# NumPad.net
KiCad netlist of a schematic drawn in EAGLE
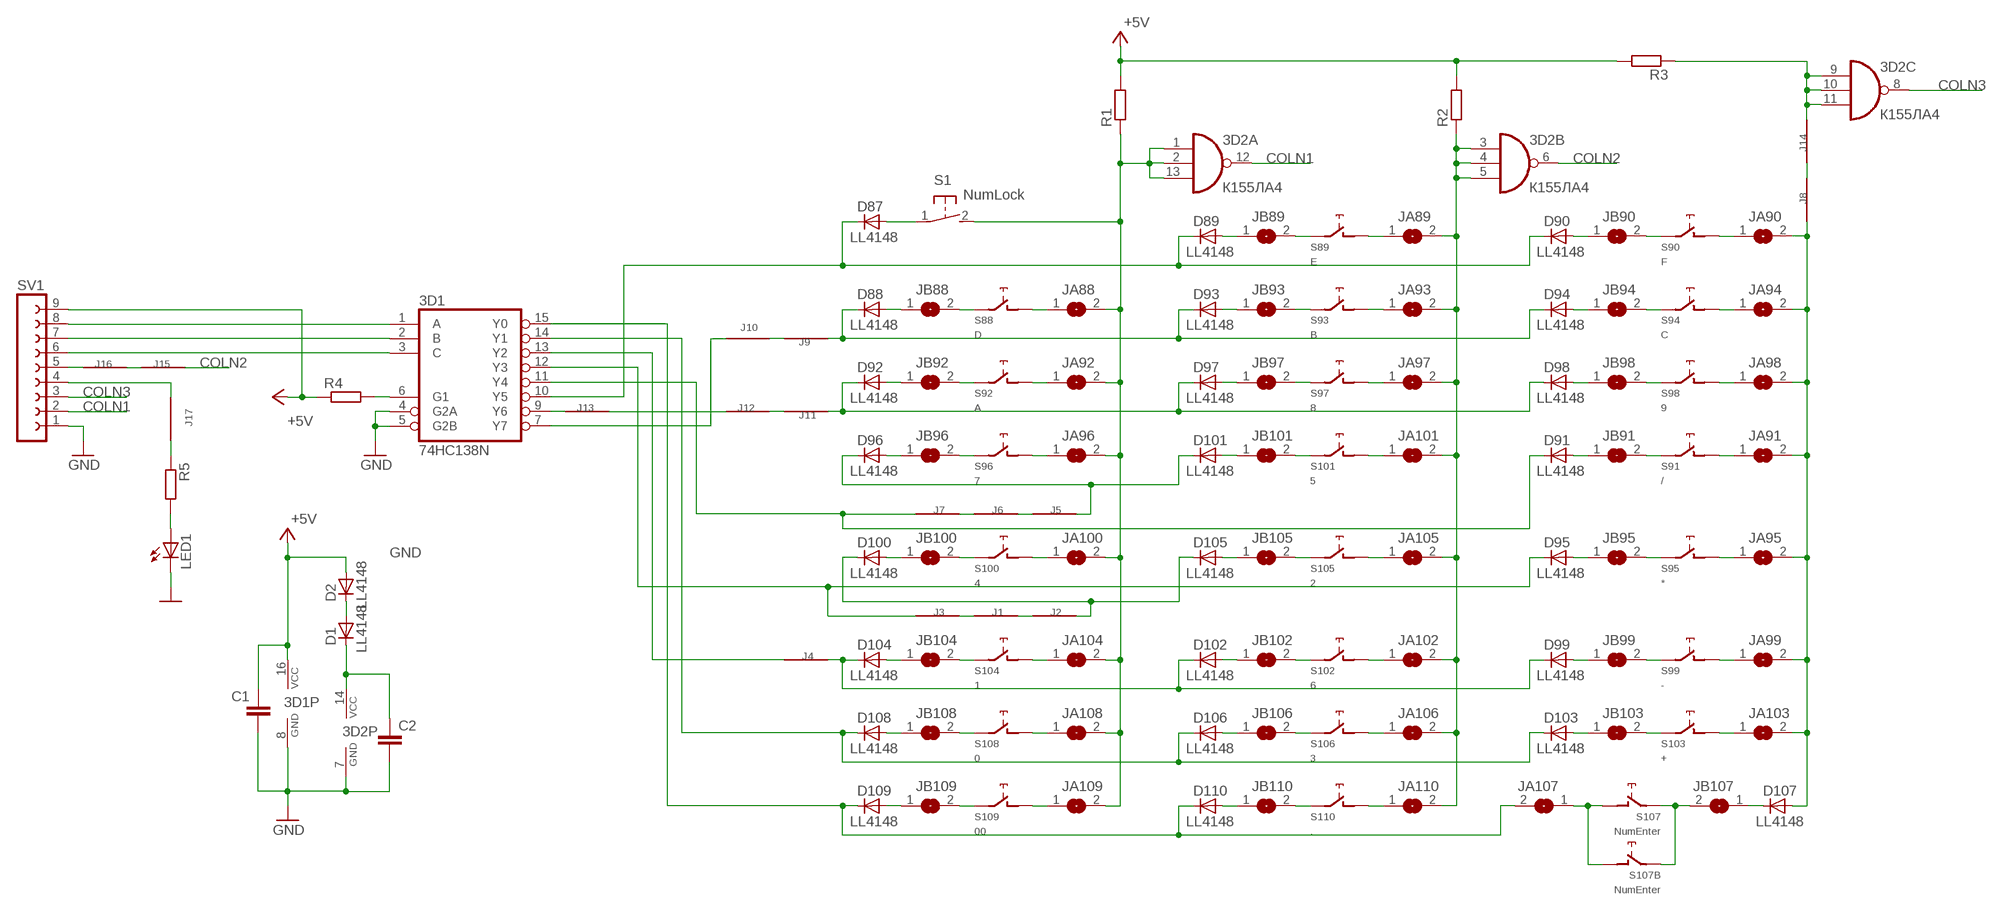
[diagram p0: schematic, sheet 1]

(export (version "E")
  (design (tool "Eeschema 10.0.6"))
  (components
    (comp (ref "3D1")
      (value "74HC138N")
      (footprint "eagle-import:DIL16")
      (libsource (lib "eagle-import") (part "74138NHC"))
    )
    (comp (ref "3D2")
      (value "К155ЛА4")
      (footprint "eagle-import:DIL14")
      (libsource (lib "eagle-import") (part "7410NHC"))
    )
    (comp (ref "C1")
      (value "C-EUC1206")
      (footprint "eagle-import:C1206")
      (libsource (lib "eagle-import") (part "C-EUC1206"))
    )
    (comp (ref "C2")
      (value "C-EUC1206")
      (footprint "eagle-import:C1206")
      (libsource (lib "eagle-import") (part "C-EUC1206"))
    )
    (comp (ref "D1")
      (value "LL4148")
      (footprint "eagle-import:SOD80C")
      (libsource (lib "eagle-import") (part "LL4148"))
    )
    (comp (ref "D2")
      (value "LL4148")
      (footprint "eagle-import:SOD80C")
      (libsource (lib "eagle-import") (part "LL4148"))
    )
    (comp (ref "D87")
      (value "LL4148")
      (footprint "eagle-import:SOD80C")
      (libsource (lib "eagle-import") (part "LL4148"))
    )
    (comp (ref "D88")
      (value "LL4148")
      (footprint "eagle-import:SOD80C")
      (libsource (lib "eagle-import") (part "LL4148"))
    )
    (comp (ref "D89")
      (value "LL4148")
      (footprint "eagle-import:SOD80C")
      (libsource (lib "eagle-import") (part "LL4148"))
    )
    (comp (ref "D90")
      (value "LL4148")
      (footprint "eagle-import:SOD80C")
      (libsource (lib "eagle-import") (part "LL4148"))
    )
    (comp (ref "D91")
      (value "LL4148")
      (footprint "eagle-import:SOD80C")
      (libsource (lib "eagle-import") (part "LL4148"))
    )
    (comp (ref "D92")
      (value "LL4148")
      (footprint "eagle-import:SOD80C")
      (libsource (lib "eagle-import") (part "LL4148"))
    )
    (comp (ref "D93")
      (value "LL4148")
      (footprint "eagle-import:SOD80C")
      (libsource (lib "eagle-import") (part "LL4148"))
    )
    (comp (ref "D94")
      (value "LL4148")
      (footprint "eagle-import:SOD80C")
      (libsource (lib "eagle-import") (part "LL4148"))
    )
    (comp (ref "D95")
      (value "LL4148")
      (footprint "eagle-import:SOD80C")
      (libsource (lib "eagle-import") (part "LL4148"))
    )
    (comp (ref "D96")
      (value "LL4148")
      (footprint "eagle-import:SOD80C")
      (libsource (lib "eagle-import") (part "LL4148"))
    )
    (comp (ref "D97")
      (value "LL4148")
      (footprint "eagle-import:SOD80C")
      (libsource (lib "eagle-import") (part "LL4148"))
    )
    (comp (ref "D98")
      (value "LL4148")
      (footprint "eagle-import:SOD80C")
      (libsource (lib "eagle-import") (part "LL4148"))
    )
    (comp (ref "D99")
      (value "LL4148")
      (footprint "eagle-import:SOD80C")
      (libsource (lib "eagle-import") (part "LL4148"))
    )
    (comp (ref "D100")
      (value "LL4148")
      (footprint "eagle-import:SOD80C")
      (libsource (lib "eagle-import") (part "LL4148"))
    )
    (comp (ref "D101")
      (value "LL4148")
      (footprint "eagle-import:SOD80C")
      (libsource (lib "eagle-import") (part "LL4148"))
    )
    (comp (ref "D102")
      (value "LL4148")
      (footprint "eagle-import:SOD80C")
      (libsource (lib "eagle-import") (part "LL4148"))
    )
    (comp (ref "D103")
      (value "LL4148")
      (footprint "eagle-import:SOD80C")
      (libsource (lib "eagle-import") (part "LL4148"))
    )
    (comp (ref "D104")
      (value "LL4148")
      (footprint "eagle-import:SOD80C")
      (libsource (lib "eagle-import") (part "LL4148"))
    )
    (comp (ref "D105")
      (value "LL4148")
      (footprint "eagle-import:SOD80C")
      (libsource (lib "eagle-import") (part "LL4148"))
    )
    (comp (ref "D106")
      (value "LL4148")
      (footprint "eagle-import:SOD80C")
      (libsource (lib "eagle-import") (part "LL4148"))
    )
    (comp (ref "D107")
      (value "LL4148")
      (footprint "eagle-import:SOD80C")
      (libsource (lib "eagle-import") (part "LL4148"))
    )
    (comp (ref "D108")
      (value "LL4148")
      (footprint "eagle-import:SOD80C")
      (libsource (lib "eagle-import") (part "LL4148"))
    )
    (comp (ref "D109")
      (value "LL4148")
      (footprint "eagle-import:SOD80C")
      (libsource (lib "eagle-import") (part "LL4148"))
    )
    (comp (ref "D110")
      (value "LL4148")
      (footprint "eagle-import:SOD80C")
      (libsource (lib "eagle-import") (part "LL4148"))
    )
    (comp (ref "J1")
      (value "J")
      (footprint "eagle-import:R1206W")
      (libsource (lib "eagle-import") (part "J"))
    )
    (comp (ref "J2")
      (value "J")
      (footprint "eagle-import:R1206W")
      (libsource (lib "eagle-import") (part "J"))
    )
    (comp (ref "J3")
      (value "J")
      (footprint "eagle-import:R1206W")
      (libsource (lib "eagle-import") (part "J"))
    )
    (comp (ref "J4")
      (value "J")
      (footprint "eagle-import:R1206W")
      (libsource (lib "eagle-import") (part "J"))
    )
    (comp (ref "J5")
      (value "J")
      (footprint "eagle-import:R1206W")
      (libsource (lib "eagle-import") (part "J"))
    )
    (comp (ref "J6")
      (value "J")
      (footprint "eagle-import:R1206W")
      (libsource (lib "eagle-import") (part "J"))
    )
    (comp (ref "J7")
      (value "J")
      (footprint "eagle-import:R1206W")
      (libsource (lib "eagle-import") (part "J"))
    )
    (comp (ref "J8")
      (value "J")
      (footprint "eagle-import:R1206W")
      (libsource (lib "eagle-import") (part "J"))
    )
    (comp (ref "J9")
      (value "J")
      (footprint "eagle-import:R1206W")
      (libsource (lib "eagle-import") (part "J"))
    )
    (comp (ref "J10")
      (value "J")
      (footprint "eagle-import:R1206W")
      (libsource (lib "eagle-import") (part "J"))
    )
    (comp (ref "J11")
      (value "J")
      (footprint "eagle-import:R1206W")
      (libsource (lib "eagle-import") (part "J"))
    )
    (comp (ref "J12")
      (value "J")
      (footprint "eagle-import:R1206W")
      (libsource (lib "eagle-import") (part "J"))
    )
    (comp (ref "J13")
      (value "J")
      (footprint "eagle-import:R1206W")
      (libsource (lib "eagle-import") (part "J"))
    )
    (comp (ref "J14")
      (value "J")
      (footprint "eagle-import:R1206W")
      (libsource (lib "eagle-import") (part "J"))
    )
    (comp (ref "J15")
      (value "J")
      (footprint "eagle-import:R1206W")
      (libsource (lib "eagle-import") (part "J"))
    )
    (comp (ref "J16")
      (value "J")
      (footprint "eagle-import:R1206W")
      (libsource (lib "eagle-import") (part "J"))
    )
    (comp (ref "J17")
      (value "J")
      (footprint "eagle-import:R1206W")
      (libsource (lib "eagle-import") (part "J"))
    )
    (comp (ref "JA88")
      (value "SJ")
      (footprint "eagle-import:SJ")
      (libsource (lib "eagle-import") (part "SJ"))
    )
    (comp (ref "JA89")
      (value "SJ")
      (footprint "eagle-import:SJ")
      (libsource (lib "eagle-import") (part "SJ"))
    )
    (comp (ref "JA90")
      (value "SJ")
      (footprint "eagle-import:SJ")
      (libsource (lib "eagle-import") (part "SJ"))
    )
    (comp (ref "JA91")
      (value "SJ")
      (footprint "eagle-import:SJ")
      (libsource (lib "eagle-import") (part "SJ"))
    )
    (comp (ref "JA92")
      (value "SJ")
      (footprint "eagle-import:SJ")
      (libsource (lib "eagle-import") (part "SJ"))
    )
    (comp (ref "JA93")
      (value "SJ")
      (footprint "eagle-import:SJ")
      (libsource (lib "eagle-import") (part "SJ"))
    )
    (comp (ref "JA94")
      (value "SJ")
      (footprint "eagle-import:SJ")
      (libsource (lib "eagle-import") (part "SJ"))
    )
    (comp (ref "JA95")
      (value "SJ")
      (footprint "eagle-import:SJ")
      (libsource (lib "eagle-import") (part "SJ"))
    )
    (comp (ref "JA96")
      (value "SJ")
      (footprint "eagle-import:SJ")
      (libsource (lib "eagle-import") (part "SJ"))
    )
    (comp (ref "JA97")
      (value "SJ")
      (footprint "eagle-import:SJ")
      (libsource (lib "eagle-import") (part "SJ"))
    )
    (comp (ref "JA98")
      (value "SJ")
      (footprint "eagle-import:SJ")
      (libsource (lib "eagle-import") (part "SJ"))
    )
    (comp (ref "JA99")
      (value "SJ")
      (footprint "eagle-import:SJ")
      (libsource (lib "eagle-import") (part "SJ"))
    )
    (comp (ref "JA100")
      (value "SJ")
      (footprint "eagle-import:SJ")
      (libsource (lib "eagle-import") (part "SJ"))
    )
    (comp (ref "JA101")
      (value "SJ")
      (footprint "eagle-import:SJ")
      (libsource (lib "eagle-import") (part "SJ"))
    )
    (comp (ref "JA102")
      (value "SJ")
      (footprint "eagle-import:SJ")
      (libsource (lib "eagle-import") (part "SJ"))
    )
    (comp (ref "JA103")
      (value "SJ")
      (footprint "eagle-import:SJ")
      (libsource (lib "eagle-import") (part "SJ"))
    )
    (comp (ref "JA104")
      (value "SJ")
      (footprint "eagle-import:SJ")
      (libsource (lib "eagle-import") (part "SJ"))
    )
    (comp (ref "JA105")
      (value "SJ")
      (footprint "eagle-import:SJ")
      (libsource (lib "eagle-import") (part "SJ"))
    )
    (comp (ref "JA106")
      (value "SJ")
      (footprint "eagle-import:SJ")
      (libsource (lib "eagle-import") (part "SJ"))
    )
    (comp (ref "JA107")
      (value "SJ")
      (footprint "eagle-import:SJ")
      (libsource (lib "eagle-import") (part "SJ"))
    )
    (comp (ref "JA108")
      (value "SJ")
      (footprint "eagle-import:SJ")
      (libsource (lib "eagle-import") (part "SJ"))
    )
    (comp (ref "JA109")
      (value "SJ")
      (footprint "eagle-import:SJ")
      (libsource (lib "eagle-import") (part "SJ"))
    )
    (comp (ref "JA110")
      (value "SJ")
      (footprint "eagle-import:SJ")
      (libsource (lib "eagle-import") (part "SJ"))
    )
    (comp (ref "JB88")
      (value "SJ")
      (footprint "eagle-import:SJ")
      (libsource (lib "eagle-import") (part "SJ"))
    )
    (comp (ref "JB89")
      (value "SJ")
      (footprint "eagle-import:SJ")
      (libsource (lib "eagle-import") (part "SJ"))
    )
    (comp (ref "JB90")
      (value "SJ")
      (footprint "eagle-import:SJ")
      (libsource (lib "eagle-import") (part "SJ"))
    )
    (comp (ref "JB91")
      (value "SJ")
      (footprint "eagle-import:SJ")
      (libsource (lib "eagle-import") (part "SJ"))
    )
    (comp (ref "JB92")
      (value "SJ")
      (footprint "eagle-import:SJ")
      (libsource (lib "eagle-import") (part "SJ"))
    )
    (comp (ref "JB93")
      (value "SJ")
      (footprint "eagle-import:SJ")
      (libsource (lib "eagle-import") (part "SJ"))
    )
    (comp (ref "JB94")
      (value "SJ")
      (footprint "eagle-import:SJ")
      (libsource (lib "eagle-import") (part "SJ"))
    )
    (comp (ref "JB95")
      (value "SJ")
      (footprint "eagle-import:SJ")
      (libsource (lib "eagle-import") (part "SJ"))
    )
    (comp (ref "JB96")
      (value "SJ")
      (footprint "eagle-import:SJ")
      (libsource (lib "eagle-import") (part "SJ"))
    )
    (comp (ref "JB97")
      (value "SJ")
      (footprint "eagle-import:SJ")
      (libsource (lib "eagle-import") (part "SJ"))
    )
    (comp (ref "JB98")
      (value "SJ")
      (footprint "eagle-import:SJ")
      (libsource (lib "eagle-import") (part "SJ"))
    )
    (comp (ref "JB99")
      (value "SJ")
      (footprint "eagle-import:SJ")
      (libsource (lib "eagle-import") (part "SJ"))
    )
    (comp (ref "JB100")
      (value "SJ")
      (footprint "eagle-import:SJ")
      (libsource (lib "eagle-import") (part "SJ"))
    )
    (comp (ref "JB101")
      (value "SJ")
      (footprint "eagle-import:SJ")
      (libsource (lib "eagle-import") (part "SJ"))
    )
    (comp (ref "JB102")
      (value "SJ")
      (footprint "eagle-import:SJ")
      (libsource (lib "eagle-import") (part "SJ"))
    )
    (comp (ref "JB103")
      (value "SJ")
      (footprint "eagle-import:SJ")
      (libsource (lib "eagle-import") (part "SJ"))
    )
    (comp (ref "JB104")
      (value "SJ")
      (footprint "eagle-import:SJ")
      (libsource (lib "eagle-import") (part "SJ"))
    )
    (comp (ref "JB105")
      (value "SJ")
      (footprint "eagle-import:SJ")
      (libsource (lib "eagle-import") (part "SJ"))
    )
    (comp (ref "JB106")
      (value "SJ")
      (footprint "eagle-import:SJ")
      (libsource (lib "eagle-import") (part "SJ"))
    )
    (comp (ref "JB107")
      (value "SJ")
      (footprint "eagle-import:SJ")
      (libsource (lib "eagle-import") (part "SJ"))
    )
    (comp (ref "JB108")
      (value "SJ")
      (footprint "eagle-import:SJ")
      (libsource (lib "eagle-import") (part "SJ"))
    )
    (comp (ref "JB109")
      (value "SJ")
      (footprint "eagle-import:SJ")
      (libsource (lib "eagle-import") (part "SJ"))
    )
    (comp (ref "JB110")
      (value "SJ")
      (footprint "eagle-import:SJ")
      (libsource (lib "eagle-import") (part "SJ"))
    )
    (comp (ref "LED1")
      (value "LED5MM")
      (footprint "eagle-import:LED5MM")
      (libsource (lib "eagle-import") (part "LED5MM"))
    )
    (comp (ref "R1")
      (value "R-EU_R1206W")
      (footprint "eagle-import:R1206W")
      (libsource (lib "eagle-import") (part "R-EU_R1206W"))
    )
    (comp (ref "R2")
      (value "R-EU_R1206W")
      (footprint "eagle-import:R1206W")
      (libsource (lib "eagle-import") (part "R-EU_R1206W"))
    )
    (comp (ref "R3")
      (value "R-EU_R1206W")
      (footprint "eagle-import:R1206W")
      (libsource (lib "eagle-import") (part "R-EU_R1206W"))
    )
    (comp (ref "R4")
      (value "R-EU_R1206W")
      (footprint "eagle-import:R1206W")
      (libsource (lib "eagle-import") (part "R-EU_R1206W"))
    )
    (comp (ref "R5")
      (value "R-EU_R1206W")
      (footprint "eagle-import:R1206W")
      (libsource (lib "eagle-import") (part "R-EU_R1206W"))
    )
    (comp (ref "S1")
      (value "NumLock")
      (footprint "eagle-import:B3F-31XX")
      (fields (field (name "MPN") "B3F-3100"))
      (libsource (lib "eagle-import") (part "31-XX"))
    )
    (comp (ref "S88")
      (value "D")
      (footprint "eagle-import:CHERRY-MX-4P")
      (libsource (lib "eagle-import") (part "CHERRY-MX-4P"))
    )
    (comp (ref "S89")
      (value "E")
      (footprint "eagle-import:CHERRY-MX-4P")
      (libsource (lib "eagle-import") (part "CHERRY-MX-4P"))
    )
    (comp (ref "S90")
      (value "F")
      (footprint "eagle-import:CHERRY-MX-4P")
      (libsource (lib "eagle-import") (part "CHERRY-MX-4P"))
    )
    (comp (ref "S91")
      (value "/")
      (footprint "eagle-import:CHERRY-MX-4P")
      (libsource (lib "eagle-import") (part "CHERRY-MX-4P"))
    )
    (comp (ref "S92")
      (value "A")
      (footprint "eagle-import:CHERRY-MX-4P")
      (libsource (lib "eagle-import") (part "CHERRY-MX-4P"))
    )
    (comp (ref "S93")
      (value "B")
      (footprint "eagle-import:CHERRY-MX-4P")
      (libsource (lib "eagle-import") (part "CHERRY-MX-4P"))
    )
    (comp (ref "S94")
      (value "C")
      (footprint "eagle-import:CHERRY-MX-4P")
      (libsource (lib "eagle-import") (part "CHERRY-MX-4P"))
    )
    (comp (ref "S95")
      (value "*")
      (footprint "eagle-import:CHERRY-MX-4P")
      (libsource (lib "eagle-import") (part "CHERRY-MX-4P"))
    )
    (comp (ref "S96")
      (value "7")
      (footprint "eagle-import:CHERRY-MX-4P")
      (libsource (lib "eagle-import") (part "CHERRY-MX-4P"))
    )
    (comp (ref "S97")
      (value "8")
      (footprint "eagle-import:CHERRY-MX-4P")
      (libsource (lib "eagle-import") (part "CHERRY-MX-4P"))
    )
    (comp (ref "S98")
      (value "9")
      (footprint "eagle-import:CHERRY-MX-4P")
      (libsource (lib "eagle-import") (part "CHERRY-MX-4P"))
    )
    (comp (ref "S99")
      (value "-")
      (footprint "eagle-import:CHERRY-MX-4P")
      (libsource (lib "eagle-import") (part "CHERRY-MX-4P"))
    )
    (comp (ref "S100")
      (value "4")
      (footprint "eagle-import:CHERRY-MX-4P")
      (libsource (lib "eagle-import") (part "CHERRY-MX-4P"))
    )
    (comp (ref "S101")
      (value "5")
      (footprint "eagle-import:CHERRY-MX-4P")
      (libsource (lib "eagle-import") (part "CHERRY-MX-4P"))
    )
    (comp (ref "S102")
      (value "6")
      (footprint "eagle-import:CHERRY-MX-4P")
      (libsource (lib "eagle-import") (part "CHERRY-MX-4P"))
    )
    (comp (ref "S103")
      (value "+")
      (footprint "eagle-import:CHERRY-MX-4P")
      (libsource (lib "eagle-import") (part "CHERRY-MX-4P"))
    )
    (comp (ref "S104")
      (value "1")
      (footprint "eagle-import:CHERRY-MX-4P")
      (libsource (lib "eagle-import") (part "CHERRY-MX-4P"))
    )
    (comp (ref "S105")
      (value "2")
      (footprint "eagle-import:CHERRY-MX-4P")
      (libsource (lib "eagle-import") (part "CHERRY-MX-4P"))
    )
    (comp (ref "S106")
      (value "3")
      (footprint "eagle-import:CHERRY-MX-4P")
      (libsource (lib "eagle-import") (part "CHERRY-MX-4P"))
    )
    (comp (ref "S107")
      (value "NumEnter")
      (footprint "eagle-import:CHERRY-MX-4P")
      (libsource (lib "eagle-import") (part "CHERRY-MX-4P"))
    )
    (comp (ref "S107B")
      (value "NumEnter")
      (footprint "eagle-import:CHERRY-MX-4P")
      (libsource (lib "eagle-import") (part "CHERRY-MX-4P"))
    )
    (comp (ref "S108")
      (value "0")
      (footprint "eagle-import:CHERRY-MX-4P")
      (libsource (lib "eagle-import") (part "CHERRY-MX-4P"))
    )
    (comp (ref "S109")
      (value "00")
      (footprint "eagle-import:CHERRY-MX-4P")
      (libsource (lib "eagle-import") (part "CHERRY-MX-4P"))
    )
    (comp (ref "S110")
      (value ".")
      (footprint "eagle-import:CHERRY-MX-4P")
      (libsource (lib "eagle-import") (part "CHERRY-MX-4P"))
    )
    (comp (ref "SV1")
      (value "FE09-1")
      (footprint "eagle-import:FE09")
      (libsource (lib "eagle-import") (part "FE09-1"))
    )
  )
  (nets
    (net (code "1") (name "+5V") (class "Default")
      (node (ref "3D1") (pin "16") (pinfunction "VCC_16") (pintype "power_in"))
      (node (ref "C1") (pin "1") (pinfunction "1_1") (pintype "passive"))
      (node (ref "D2") (pin "A") (pinfunction "A_A") (pintype "passive"))
      (node (ref "R1") (pin "2") (pinfunction "2_2") (pintype "passive"))
      (node (ref "R2") (pin "2") (pinfunction "2_2") (pintype "passive"))
      (node (ref "R3") (pin "2") (pinfunction "2_2") (pintype "passive"))
      (node (ref "R4") (pin "1") (pinfunction "1_1") (pintype "passive"))
      (node (ref "SV1") (pin "9") (pinfunction "9_9") (pintype "passive"))
    )
    (net (code "2") (name "/COLN1") (class "Default")
      (node (ref "3D2") (pin "12") (pinfunction "O_12") (pintype "output"))
      (node (ref "SV1") (pin "2") (pinfunction "2_2") (pintype "passive"))
    )
    (net (code "3") (name "/COLN2") (class "Default")
      (node (ref "3D2") (pin "6") (pinfunction "O_6") (pintype "output"))
      (node (ref "J15") (pin "1") (pinfunction "P$1_1") (pintype "bidirectional"))
    )
    (net (code "4") (name "/COLN3") (class "Default")
      (node (ref "3D2") (pin "8") (pinfunction "O_8") (pintype "output"))
      (node (ref "SV1") (pin "3") (pinfunction "3_3") (pintype "passive"))
    )
    (net (code "5") (name "GND") (class "Default")
      (node (ref "3D1") (pin "4") (pinfunction "G2A_4") (pintype "input"))
      (node (ref "3D1") (pin "5") (pinfunction "G2B_5") (pintype "input"))
      (node (ref "3D1") (pin "8") (pinfunction "GND_8") (pintype "power_in"))
      (node (ref "3D2") (pin "7") (pinfunction "GND_7") (pintype "power_in"))
      (node (ref "C1") (pin "2") (pinfunction "2_2") (pintype "passive"))
      (node (ref "C2") (pin "2") (pinfunction "2_2") (pintype "passive"))
      (node (ref "LED1") (pin "K") (pinfunction "C_K") (pintype "passive"))
      (node (ref "SV1") (pin "1") (pinfunction "1_1") (pintype "passive"))
    )
    (net (code "6") (name "Net-(3D1A-A)") (class "Default")
      (node (ref "3D1") (pin "1") (pinfunction "A_1") (pintype "input"))
      (node (ref "SV1") (pin "8") (pinfunction "8_8") (pintype "passive"))
    )
    (net (code "7") (name "Net-(3D1A-B)") (class "Default")
      (node (ref "3D1") (pin "2") (pinfunction "B_2") (pintype "input"))
      (node (ref "SV1") (pin "7") (pinfunction "7_7") (pintype "passive"))
    )
    (net (code "8") (name "Net-(3D1A-C)") (class "Default")
      (node (ref "3D1") (pin "3") (pinfunction "C_3") (pintype "input"))
      (node (ref "SV1") (pin "6") (pinfunction "6_6") (pintype "passive"))
    )
    (net (code "9") (name "Net-(3D1A-G1)") (class "Default")
      (node (ref "3D1") (pin "6") (pinfunction "G1_6") (pintype "input"))
      (node (ref "R4") (pin "2") (pinfunction "2_2") (pintype "passive"))
    )
    (net (code "10") (name "Net-(3D1A-Y0)") (class "Default")
      (node (ref "3D1") (pin "15") (pinfunction "Y0_15") (pintype "output"))
      (node (ref "D109") (pin "C") (pinfunction "C_C") (pintype "passive"))
      (node (ref "D110") (pin "C") (pinfunction "C_C") (pintype "passive"))
      (node (ref "JA107") (pin "2") (pinfunction "2_2") (pintype "passive"))
    )
    (net (code "11") (name "Net-(3D1A-Y1)") (class "Default")
      (node (ref "3D1") (pin "14") (pinfunction "Y1_14") (pintype "output"))
      (node (ref "D103") (pin "C") (pinfunction "C_C") (pintype "passive"))
      (node (ref "D106") (pin "C") (pinfunction "C_C") (pintype "passive"))
      (node (ref "D108") (pin "C") (pinfunction "C_C") (pintype "passive"))
    )
    (net (code "12") (name "Net-(3D1A-Y2)") (class "Default")
      (node (ref "3D1") (pin "13") (pinfunction "Y2_13") (pintype "output"))
      (node (ref "J4") (pin "2") (pinfunction "P$2_2") (pintype "bidirectional"))
    )
    (net (code "13") (name "Net-(3D1A-Y3)") (class "Default")
      (node (ref "3D1") (pin "12") (pinfunction "Y3_12") (pintype "output"))
      (node (ref "D95") (pin "C") (pinfunction "C_C") (pintype "passive"))
      (node (ref "J3") (pin "2") (pinfunction "P$2_2") (pintype "bidirectional"))
    )
    (net (code "14") (name "Net-(3D1A-Y4)") (class "Default")
      (node (ref "3D1") (pin "11") (pinfunction "Y4_11") (pintype "output"))
      (node (ref "D91") (pin "C") (pinfunction "C_C") (pintype "passive"))
      (node (ref "J7") (pin "2") (pinfunction "P$2_2") (pintype "bidirectional"))
    )
    (net (code "15") (name "Net-(3D1A-Y5)") (class "Default")
      (node (ref "3D1") (pin "10") (pinfunction "Y5_10") (pintype "output"))
      (node (ref "D87") (pin "C") (pinfunction "C_C") (pintype "passive"))
      (node (ref "D89") (pin "C") (pinfunction "C_C") (pintype "passive"))
      (node (ref "D90") (pin "C") (pinfunction "C_C") (pintype "passive"))
    )
    (net (code "16") (name "Net-(3D1A-Y6)") (class "Default")
      (node (ref "3D1") (pin "9") (pinfunction "Y6_9") (pintype "output"))
      (node (ref "J13") (pin "2") (pinfunction "P$2_2") (pintype "bidirectional"))
    )
    (net (code "17") (name "Net-(3D1A-Y7)") (class "Default")
      (node (ref "3D1") (pin "7") (pinfunction "Y7_7") (pintype "output"))
      (node (ref "J10") (pin "1") (pinfunction "P$1_1") (pintype "bidirectional"))
    )
    (net (code "18") (name "Net-(3D2A-I0)") (class "Default")
      (node (ref "3D2") (pin "1") (pinfunction "I0_1") (pintype "input"))
      (node (ref "3D2") (pin "13") (pinfunction "I2_13") (pintype "input"))
      (node (ref "3D2") (pin "2") (pinfunction "I1_2") (pintype "input"))
      (node (ref "JA100") (pin "2") (pinfunction "2_2") (pintype "passive"))
      (node (ref "JA104") (pin "2") (pinfunction "2_2") (pintype "passive"))
      (node (ref "JA108") (pin "2") (pinfunction "2_2") (pintype "passive"))
      (node (ref "JA109") (pin "2") (pinfunction "2_2") (pintype "passive"))
      (node (ref "JA88") (pin "2") (pinfunction "2_2") (pintype "passive"))
      (node (ref "JA92") (pin "2") (pinfunction "2_2") (pintype "passive"))
      (node (ref "JA96") (pin "2") (pinfunction "2_2") (pintype "passive"))
      (node (ref "R1") (pin "1") (pinfunction "1_1") (pintype "passive"))
      (node (ref "S1") (pin "2") (pinfunction "S_2") (pintype "passive"))
    )
    (net (code "19") (name "Net-(3D2B-I0)") (class "Default")
      (node (ref "3D2") (pin "3") (pinfunction "I0_3") (pintype "input"))
      (node (ref "3D2") (pin "4") (pinfunction "I1_4") (pintype "input"))
      (node (ref "3D2") (pin "5") (pinfunction "I2_5") (pintype "input"))
      (node (ref "JA101") (pin "2") (pinfunction "2_2") (pintype "passive"))
      (node (ref "JA102") (pin "2") (pinfunction "2_2") (pintype "passive"))
      (node (ref "JA105") (pin "2") (pinfunction "2_2") (pintype "passive"))
      (node (ref "JA106") (pin "2") (pinfunction "2_2") (pintype "passive"))
      (node (ref "JA110") (pin "2") (pinfunction "2_2") (pintype "passive"))
      (node (ref "JA89") (pin "2") (pinfunction "2_2") (pintype "passive"))
      (node (ref "JA93") (pin "2") (pinfunction "2_2") (pintype "passive"))
      (node (ref "JA97") (pin "2") (pinfunction "2_2") (pintype "passive"))
      (node (ref "R2") (pin "1") (pinfunction "1_1") (pintype "passive"))
    )
    (net (code "20") (name "Net-(3D2C-I0)") (class "Default")
      (node (ref "3D2") (pin "10") (pinfunction "I1_10") (pintype "input"))
      (node (ref "3D2") (pin "11") (pinfunction "I2_11") (pintype "input"))
      (node (ref "3D2") (pin "9") (pinfunction "I0_9") (pintype "input"))
      (node (ref "J14") (pin "1") (pinfunction "P$1_1") (pintype "bidirectional"))
      (node (ref "R3") (pin "1") (pinfunction "1_1") (pintype "passive"))
    )
    (net (code "21") (name "Net-(3D2D-VCC)") (class "Default")
      (node (ref "3D2") (pin "14") (pinfunction "VCC_14") (pintype "power_in"))
      (node (ref "C2") (pin "1") (pinfunction "1_1") (pintype "passive"))
      (node (ref "D1") (pin "C") (pinfunction "C_C") (pintype "passive"))
    )
    (net (code "22") (name "Net-(D1-PadA)") (class "Default")
      (node (ref "D1") (pin "A") (pinfunction "A_A") (pintype "passive"))
      (node (ref "D2") (pin "C") (pinfunction "C_C") (pintype "passive"))
    )
    (net (code "23") (name "Net-(D88-PadA)") (class "Default")
      (node (ref "D88") (pin "A") (pinfunction "A_A") (pintype "passive"))
      (node (ref "JB88") (pin "1") (pinfunction "1_1") (pintype "passive"))
    )
    (net (code "24") (name "Net-(D89-PadA)") (class "Default")
      (node (ref "D89") (pin "A") (pinfunction "A_A") (pintype "passive"))
      (node (ref "JB89") (pin "1") (pinfunction "1_1") (pintype "passive"))
    )
    (net (code "25") (name "Net-(D90-PadA)") (class "Default")
      (node (ref "D90") (pin "A") (pinfunction "A_A") (pintype "passive"))
      (node (ref "JB90") (pin "1") (pinfunction "1_1") (pintype "passive"))
    )
    (net (code "26") (name "Net-(D91-PadA)") (class "Default")
      (node (ref "D91") (pin "A") (pinfunction "A_A") (pintype "passive"))
      (node (ref "JB91") (pin "1") (pinfunction "1_1") (pintype "passive"))
    )
    (net (code "27") (name "Net-(D92-PadA)") (class "Default")
      (node (ref "D92") (pin "A") (pinfunction "A_A") (pintype "passive"))
      (node (ref "JB92") (pin "1") (pinfunction "1_1") (pintype "passive"))
    )
    (net (code "28") (name "Net-(D93-PadA)") (class "Default")
      (node (ref "D93") (pin "A") (pinfunction "A_A") (pintype "passive"))
      (node (ref "JB93") (pin "1") (pinfunction "1_1") (pintype "passive"))
    )
    (net (code "29") (name "Net-(D94-PadA)") (class "Default")
      (node (ref "D94") (pin "A") (pinfunction "A_A") (pintype "passive"))
      (node (ref "JB94") (pin "1") (pinfunction "1_1") (pintype "passive"))
    )
    (net (code "30") (name "Net-(D95-PadA)") (class "Default")
      (node (ref "D95") (pin "A") (pinfunction "A_A") (pintype "passive"))
      (node (ref "JB95") (pin "1") (pinfunction "1_1") (pintype "passive"))
    )
    (net (code "31") (name "Net-(D96-PadA)") (class "Default")
      (node (ref "D96") (pin "A") (pinfunction "A_A") (pintype "passive"))
      (node (ref "JB96") (pin "1") (pinfunction "1_1") (pintype "passive"))
    )
    (net (code "32") (name "Net-(D97-PadA)") (class "Default")
      (node (ref "D97") (pin "A") (pinfunction "A_A") (pintype "passive"))
      (node (ref "JB97") (pin "1") (pinfunction "1_1") (pintype "passive"))
    )
    (net (code "33") (name "Net-(D98-PadA)") (class "Default")
      (node (ref "D98") (pin "A") (pinfunction "A_A") (pintype "passive"))
      (node (ref "JB98") (pin "1") (pinfunction "1_1") (pintype "passive"))
    )
    (net (code "34") (name "Net-(D99-PadA)") (class "Default")
      (node (ref "D99") (pin "A") (pinfunction "A_A") (pintype "passive"))
      (node (ref "JB99") (pin "1") (pinfunction "1_1") (pintype "passive"))
    )
    (net (code "35") (name "Net-(D100-PadA)") (class "Default")
      (node (ref "D100") (pin "A") (pinfunction "A_A") (pintype "passive"))
      (node (ref "JB100") (pin "1") (pinfunction "1_1") (pintype "passive"))
    )
    (net (code "36") (name "Net-(D101-PadA)") (class "Default")
      (node (ref "D101") (pin "A") (pinfunction "A_A") (pintype "passive"))
      (node (ref "JB101") (pin "1") (pinfunction "1_1") (pintype "passive"))
    )
    (net (code "37") (name "Net-(D102-PadA)") (class "Default")
      (node (ref "D102") (pin "A") (pinfunction "A_A") (pintype "passive"))
      (node (ref "JB102") (pin "1") (pinfunction "1_1") (pintype "passive"))
    )
    (net (code "38") (name "Net-(D103-PadA)") (class "Default")
      (node (ref "D103") (pin "A") (pinfunction "A_A") (pintype "passive"))
      (node (ref "JB103") (pin "1") (pinfunction "1_1") (pintype "passive"))
    )
    (net (code "39") (name "Net-(D104-PadA)") (class "Default")
      (node (ref "D104") (pin "A") (pinfunction "A_A") (pintype "passive"))
      (node (ref "JB104") (pin "1") (pinfunction "1_1") (pintype "passive"))
    )
    (net (code "40") (name "Net-(D105-PadA)") (class "Default")
      (node (ref "D105") (pin "A") (pinfunction "A_A") (pintype "passive"))
      (node (ref "JB105") (pin "1") (pinfunction "1_1") (pintype "passive"))
    )
    (net (code "41") (name "Net-(D106-PadA)") (class "Default")
      (node (ref "D106") (pin "A") (pinfunction "A_A") (pintype "passive"))
      (node (ref "JB106") (pin "1") (pinfunction "1_1") (pintype "passive"))
    )
    (net (code "42") (name "Net-(D107-PadC)") (class "Default")
      (node (ref "D107") (pin "C") (pinfunction "C_C") (pintype "passive"))
      (node (ref "JB107") (pin "1") (pinfunction "1_1") (pintype "passive"))
    )
    (net (code "43") (name "Net-(D108-PadA)") (class "Default")
      (node (ref "D108") (pin "A") (pinfunction "A_A") (pintype "passive"))
      (node (ref "JB108") (pin "1") (pinfunction "1_1") (pintype "passive"))
    )
    (net (code "44") (name "Net-(D109-PadA)") (class "Default")
      (node (ref "D109") (pin "A") (pinfunction "A_A") (pintype "passive"))
      (node (ref "JB109") (pin "1") (pinfunction "1_1") (pintype "passive"))
    )
    (net (code "45") (name "Net-(D110-PadA)") (class "Default")
      (node (ref "D110") (pin "A") (pinfunction "A_A") (pintype "passive"))
      (node (ref "JB110") (pin "1") (pinfunction "1_1") (pintype "passive"))
    )
    (net (code "46") (name "Net-(J1-P$1)") (class "Default")
      (node (ref "J1") (pin "1") (pinfunction "P$1_1") (pintype "bidirectional"))
      (node (ref "J2") (pin "2") (pinfunction "P$2_2") (pintype "bidirectional"))
    )
    (net (code "47") (name "Net-(J1-P$2)") (class "Default")
      (node (ref "J1") (pin "2") (pinfunction "P$2_2") (pintype "bidirectional"))
      (node (ref "J3") (pin "1") (pinfunction "P$1_1") (pintype "bidirectional"))
    )
    (net (code "48") (name "Net-(J2-P$1)") (class "Default")
      (node (ref "D100") (pin "C") (pinfunction "C_C") (pintype "passive"))
      (node (ref "D105") (pin "C") (pinfunction "C_C") (pintype "passive"))
      (node (ref "J2") (pin "1") (pinfunction "P$1_1") (pintype "bidirectional"))
    )
    (net (code "49") (name "Net-(J4-P$1)") (class "Default")
      (node (ref "D102") (pin "C") (pinfunction "C_C") (pintype "passive"))
      (node (ref "D104") (pin "C") (pinfunction "C_C") (pintype "passive"))
      (node (ref "D99") (pin "C") (pinfunction "C_C") (pintype "passive"))
      (node (ref "J4") (pin "1") (pinfunction "P$1_1") (pintype "bidirectional"))
    )
    (net (code "50") (name "Net-(J5-P$1)") (class "Default")
      (node (ref "D101") (pin "C") (pinfunction "C_C") (pintype "passive"))
      (node (ref "D96") (pin "C") (pinfunction "C_C") (pintype "passive"))
      (node (ref "J5") (pin "1") (pinfunction "P$1_1") (pintype "bidirectional"))
    )
    (net (code "51") (name "Net-(J5-P$2)") (class "Default")
      (node (ref "J5") (pin "2") (pinfunction "P$2_2") (pintype "bidirectional"))
      (node (ref "J6") (pin "1") (pinfunction "P$1_1") (pintype "bidirectional"))
    )
    (net (code "52") (name "Net-(J6-P$2)") (class "Default")
      (node (ref "J6") (pin "2") (pinfunction "P$2_2") (pintype "bidirectional"))
      (node (ref "J7") (pin "1") (pinfunction "P$1_1") (pintype "bidirectional"))
    )
    (net (code "53") (name "Net-(J8-P$2)") (class "Default")
      (node (ref "D107") (pin "A") (pinfunction "A_A") (pintype "passive"))
      (node (ref "J8") (pin "2") (pinfunction "P$2_2") (pintype "bidirectional"))
      (node (ref "JA103") (pin "2") (pinfunction "2_2") (pintype "passive"))
      (node (ref "JA90") (pin "2") (pinfunction "2_2") (pintype "passive"))
      (node (ref "JA91") (pin "2") (pinfunction "2_2") (pintype "passive"))
      (node (ref "JA94") (pin "2") (pinfunction "2_2") (pintype "passive"))
      (node (ref "JA95") (pin "2") (pinfunction "2_2") (pintype "passive"))
      (node (ref "JA98") (pin "2") (pinfunction "2_2") (pintype "passive"))
      (node (ref "JA99") (pin "2") (pinfunction "2_2") (pintype "passive"))
    )
    (net (code "54") (name "Net-(J9-P$2)") (class "Default")
      (node (ref "D88") (pin "C") (pinfunction "C_C") (pintype "passive"))
      (node (ref "D93") (pin "C") (pinfunction "C_C") (pintype "passive"))
      (node (ref "D94") (pin "C") (pinfunction "C_C") (pintype "passive"))
      (node (ref "J9") (pin "2") (pinfunction "P$2_2") (pintype "bidirectional"))
    )
    (net (code "55") (name "Net-(J10-P$2)") (class "Default")
      (node (ref "J10") (pin "2") (pinfunction "P$2_2") (pintype "bidirectional"))
      (node (ref "J9") (pin "1") (pinfunction "P$1_1") (pintype "bidirectional"))
    )
    (net (code "56") (name "Net-(J11-P$1)") (class "Default")
      (node (ref "J11") (pin "1") (pinfunction "P$1_1") (pintype "bidirectional"))
      (node (ref "J12") (pin "1") (pinfunction "P$1_1") (pintype "bidirectional"))
    )
    (net (code "57") (name "Net-(J11-P$2)") (class "Default")
      (node (ref "D92") (pin "C") (pinfunction "C_C") (pintype "passive"))
      (node (ref "D97") (pin "C") (pinfunction "C_C") (pintype "passive"))
      (node (ref "D98") (pin "C") (pinfunction "C_C") (pintype "passive"))
      (node (ref "J11") (pin "2") (pinfunction "P$2_2") (pintype "bidirectional"))
    )
    (net (code "58") (name "Net-(J12-P$2)") (class "Default")
      (node (ref "J12") (pin "2") (pinfunction "P$2_2") (pintype "bidirectional"))
      (node (ref "J13") (pin "1") (pinfunction "P$1_1") (pintype "bidirectional"))
    )
    (net (code "59") (name "Net-(J14-P$2)") (class "Default")
      (node (ref "J14") (pin "2") (pinfunction "P$2_2") (pintype "bidirectional"))
      (node (ref "J8") (pin "1") (pinfunction "P$1_1") (pintype "bidirectional"))
    )
    (net (code "60") (name "Net-(J15-P$2)") (class "Default")
      (node (ref "J15") (pin "2") (pinfunction "P$2_2") (pintype "bidirectional"))
      (node (ref "J16") (pin "1") (pinfunction "P$1_1") (pintype "bidirectional"))
    )
    (net (code "61") (name "Net-(J16-P$2)") (class "Default")
      (node (ref "J16") (pin "2") (pinfunction "P$2_2") (pintype "bidirectional"))
      (node (ref "SV1") (pin "5") (pinfunction "5_5") (pintype "passive"))
    )
    (net (code "62") (name "Net-(J17-P$1)") (class "Default")
      (node (ref "J17") (pin "1") (pinfunction "P$1_1") (pintype "bidirectional"))
      (node (ref "R5") (pin "1") (pinfunction "1_1") (pintype "passive"))
    )
    (net (code "63") (name "Net-(J17-P$2)") (class "Default")
      (node (ref "J17") (pin "2") (pinfunction "P$2_2") (pintype "bidirectional"))
      (node (ref "SV1") (pin "4") (pinfunction "4_4") (pintype "passive"))
    )
    (net (code "64") (name "Net-(LED1-PadA)") (class "Default")
      (node (ref "LED1") (pin "A") (pinfunction "A_A") (pintype "passive"))
      (node (ref "R5") (pin "2") (pinfunction "2_2") (pintype "passive"))
    )
    (net (code "65") (name "Net-(S1-P)") (class "Default")
      (node (ref "D87") (pin "A") (pinfunction "A_A") (pintype "passive"))
      (node (ref "S1") (pin "1") (pinfunction "P_1") (pintype "passive"))
    )
    (net (code "66") (name "Net-(S88A-PIN-1)") (class "Default")
      (node (ref "JB88") (pin "2") (pinfunction "2_2") (pintype "passive"))
      (node (ref "S88") (pin "SW1") (pinfunction "PIN-1_SW1") (pintype "passive"))
    )
    (net (code "67") (name "Net-(S88A-PIN-2)") (class "Default")
      (node (ref "JA88") (pin "1") (pinfunction "1_1") (pintype "passive"))
      (node (ref "S88") (pin "SW2") (pinfunction "PIN-2_SW2") (pintype "passive"))
    )
    (net (code "68") (name "Net-(S89A-PIN-1)") (class "Default")
      (node (ref "JB89") (pin "2") (pinfunction "2_2") (pintype "passive"))
      (node (ref "S89") (pin "SW1") (pinfunction "PIN-1_SW1") (pintype "passive"))
    )
    (net (code "69") (name "Net-(S89A-PIN-2)") (class "Default")
      (node (ref "JA89") (pin "1") (pinfunction "1_1") (pintype "passive"))
      (node (ref "S89") (pin "SW2") (pinfunction "PIN-2_SW2") (pintype "passive"))
    )
    (net (code "70") (name "Net-(S90A-PIN-1)") (class "Default")
      (node (ref "JB90") (pin "2") (pinfunction "2_2") (pintype "passive"))
      (node (ref "S90") (pin "SW1") (pinfunction "PIN-1_SW1") (pintype "passive"))
    )
    (net (code "71") (name "Net-(S90A-PIN-2)") (class "Default")
      (node (ref "JA90") (pin "1") (pinfunction "1_1") (pintype "passive"))
      (node (ref "S90") (pin "SW2") (pinfunction "PIN-2_SW2") (pintype "passive"))
    )
    (net (code "72") (name "Net-(S91A-PIN-1)") (class "Default")
      (node (ref "JB91") (pin "2") (pinfunction "2_2") (pintype "passive"))
      (node (ref "S91") (pin "SW1") (pinfunction "PIN-1_SW1") (pintype "passive"))
    )
    (net (code "73") (name "Net-(S91A-PIN-2)") (class "Default")
      (node (ref "JA91") (pin "1") (pinfunction "1_1") (pintype "passive"))
      (node (ref "S91") (pin "SW2") (pinfunction "PIN-2_SW2") (pintype "passive"))
    )
    (net (code "74") (name "Net-(S92A-PIN-1)") (class "Default")
      (node (ref "JB92") (pin "2") (pinfunction "2_2") (pintype "passive"))
      (node (ref "S92") (pin "SW1") (pinfunction "PIN-1_SW1") (pintype "passive"))
    )
    (net (code "75") (name "Net-(S92A-PIN-2)") (class "Default")
      (node (ref "JA92") (pin "1") (pinfunction "1_1") (pintype "passive"))
      (node (ref "S92") (pin "SW2") (pinfunction "PIN-2_SW2") (pintype "passive"))
    )
    (net (code "76") (name "Net-(S93A-PIN-1)") (class "Default")
      (node (ref "JB93") (pin "2") (pinfunction "2_2") (pintype "passive"))
      (node (ref "S93") (pin "SW1") (pinfunction "PIN-1_SW1") (pintype "passive"))
    )
    (net (code "77") (name "Net-(S93A-PIN-2)") (class "Default")
      (node (ref "JA93") (pin "1") (pinfunction "1_1") (pintype "passive"))
      (node (ref "S93") (pin "SW2") (pinfunction "PIN-2_SW2") (pintype "passive"))
    )
    (net (code "78") (name "Net-(S94A-PIN-1)") (class "Default")
      (node (ref "JB94") (pin "2") (pinfunction "2_2") (pintype "passive"))
      (node (ref "S94") (pin "SW1") (pinfunction "PIN-1_SW1") (pintype "passive"))
    )
    (net (code "79") (name "Net-(S94A-PIN-2)") (class "Default")
      (node (ref "JA94") (pin "1") (pinfunction "1_1") (pintype "passive"))
      (node (ref "S94") (pin "SW2") (pinfunction "PIN-2_SW2") (pintype "passive"))
    )
    (net (code "80") (name "Net-(S95A-PIN-1)") (class "Default")
      (node (ref "JB95") (pin "2") (pinfunction "2_2") (pintype "passive"))
      (node (ref "S95") (pin "SW1") (pinfunction "PIN-1_SW1") (pintype "passive"))
    )
    (net (code "81") (name "Net-(S95A-PIN-2)") (class "Default")
      (node (ref "JA95") (pin "1") (pinfunction "1_1") (pintype "passive"))
      (node (ref "S95") (pin "SW2") (pinfunction "PIN-2_SW2") (pintype "passive"))
    )
    (net (code "82") (name "Net-(S96A-PIN-1)") (class "Default")
      (node (ref "JB96") (pin "2") (pinfunction "2_2") (pintype "passive"))
      (node (ref "S96") (pin "SW1") (pinfunction "PIN-1_SW1") (pintype "passive"))
    )
    (net (code "83") (name "Net-(S96A-PIN-2)") (class "Default")
      (node (ref "JA96") (pin "1") (pinfunction "1_1") (pintype "passive"))
      (node (ref "S96") (pin "SW2") (pinfunction "PIN-2_SW2") (pintype "passive"))
    )
    (net (code "84") (name "Net-(S97A-PIN-1)") (class "Default")
      (node (ref "JB97") (pin "2") (pinfunction "2_2") (pintype "passive"))
      (node (ref "S97") (pin "SW1") (pinfunction "PIN-1_SW1") (pintype "passive"))
    )
    (net (code "85") (name "Net-(S97A-PIN-2)") (class "Default")
      (node (ref "JA97") (pin "1") (pinfunction "1_1") (pintype "passive"))
      (node (ref "S97") (pin "SW2") (pinfunction "PIN-2_SW2") (pintype "passive"))
    )
    (net (code "86") (name "Net-(S98A-PIN-1)") (class "Default")
      (node (ref "JB98") (pin "2") (pinfunction "2_2") (pintype "passive"))
      (node (ref "S98") (pin "SW1") (pinfunction "PIN-1_SW1") (pintype "passive"))
    )
    (net (code "87") (name "Net-(S98A-PIN-2)") (class "Default")
      (node (ref "JA98") (pin "1") (pinfunction "1_1") (pintype "passive"))
      (node (ref "S98") (pin "SW2") (pinfunction "PIN-2_SW2") (pintype "passive"))
    )
    (net (code "88") (name "Net-(S99A-PIN-1)") (class "Default")
      (node (ref "JB99") (pin "2") (pinfunction "2_2") (pintype "passive"))
      (node (ref "S99") (pin "SW1") (pinfunction "PIN-1_SW1") (pintype "passive"))
    )
    (net (code "89") (name "Net-(S99A-PIN-2)") (class "Default")
      (node (ref "JA99") (pin "1") (pinfunction "1_1") (pintype "passive"))
      (node (ref "S99") (pin "SW2") (pinfunction "PIN-2_SW2") (pintype "passive"))
    )
    (net (code "90") (name "Net-(S100A-PIN-1)") (class "Default")
      (node (ref "JB100") (pin "2") (pinfunction "2_2") (pintype "passive"))
      (node (ref "S100") (pin "SW1") (pinfunction "PIN-1_SW1") (pintype "passive"))
    )
    (net (code "91") (name "Net-(S100A-PIN-2)") (class "Default")
      (node (ref "JA100") (pin "1") (pinfunction "1_1") (pintype "passive"))
      (node (ref "S100") (pin "SW2") (pinfunction "PIN-2_SW2") (pintype "passive"))
    )
    (net (code "92") (name "Net-(S101A-PIN-1)") (class "Default")
      (node (ref "JB101") (pin "2") (pinfunction "2_2") (pintype "passive"))
      (node (ref "S101") (pin "SW1") (pinfunction "PIN-1_SW1") (pintype "passive"))
    )
    (net (code "93") (name "Net-(S101A-PIN-2)") (class "Default")
      (node (ref "JA101") (pin "1") (pinfunction "1_1") (pintype "passive"))
      (node (ref "S101") (pin "SW2") (pinfunction "PIN-2_SW2") (pintype "passive"))
    )
    (net (code "94") (name "Net-(S102A-PIN-1)") (class "Default")
      (node (ref "JB102") (pin "2") (pinfunction "2_2") (pintype "passive"))
      (node (ref "S102") (pin "SW1") (pinfunction "PIN-1_SW1") (pintype "passive"))
    )
    (net (code "95") (name "Net-(S102A-PIN-2)") (class "Default")
      (node (ref "JA102") (pin "1") (pinfunction "1_1") (pintype "passive"))
      (node (ref "S102") (pin "SW2") (pinfunction "PIN-2_SW2") (pintype "passive"))
    )
    (net (code "96") (name "Net-(S103A-PIN-1)") (class "Default")
      (node (ref "JB103") (pin "2") (pinfunction "2_2") (pintype "passive"))
      (node (ref "S103") (pin "SW1") (pinfunction "PIN-1_SW1") (pintype "passive"))
    )
    (net (code "97") (name "Net-(S103A-PIN-2)") (class "Default")
      (node (ref "JA103") (pin "1") (pinfunction "1_1") (pintype "passive"))
      (node (ref "S103") (pin "SW2") (pinfunction "PIN-2_SW2") (pintype "passive"))
    )
    (net (code "98") (name "Net-(S104A-PIN-1)") (class "Default")
      (node (ref "JB104") (pin "2") (pinfunction "2_2") (pintype "passive"))
      (node (ref "S104") (pin "SW1") (pinfunction "PIN-1_SW1") (pintype "passive"))
    )
    (net (code "99") (name "Net-(S104A-PIN-2)") (class "Default")
      (node (ref "JA104") (pin "1") (pinfunction "1_1") (pintype "passive"))
      (node (ref "S104") (pin "SW2") (pinfunction "PIN-2_SW2") (pintype "passive"))
    )
    (net (code "100") (name "Net-(S105A-PIN-1)") (class "Default")
      (node (ref "JB105") (pin "2") (pinfunction "2_2") (pintype "passive"))
      (node (ref "S105") (pin "SW1") (pinfunction "PIN-1_SW1") (pintype "passive"))
    )
    (net (code "101") (name "Net-(S105A-PIN-2)") (class "Default")
      (node (ref "JA105") (pin "1") (pinfunction "1_1") (pintype "passive"))
      (node (ref "S105") (pin "SW2") (pinfunction "PIN-2_SW2") (pintype "passive"))
    )
    (net (code "102") (name "Net-(S106A-PIN-1)") (class "Default")
      (node (ref "JB106") (pin "2") (pinfunction "2_2") (pintype "passive"))
      (node (ref "S106") (pin "SW1") (pinfunction "PIN-1_SW1") (pintype "passive"))
    )
    (net (code "103") (name "Net-(S106A-PIN-2)") (class "Default")
      (node (ref "JA106") (pin "1") (pinfunction "1_1") (pintype "passive"))
      (node (ref "S106") (pin "SW2") (pinfunction "PIN-2_SW2") (pintype "passive"))
    )
    (net (code "104") (name "Net-(S107A-PIN-1)") (class "Default")
      (node (ref "JB107") (pin "2") (pinfunction "2_2") (pintype "passive"))
      (node (ref "S107") (pin "SW1") (pinfunction "PIN-1_SW1") (pintype "passive"))
      (node (ref "S107B") (pin "SW1") (pinfunction "PIN-1_SW1") (pintype "passive"))
    )
    (net (code "105") (name "Net-(S107A-PIN-2)") (class "Default")
      (node (ref "JA107") (pin "1") (pinfunction "1_1") (pintype "passive"))
      (node (ref "S107") (pin "SW2") (pinfunction "PIN-2_SW2") (pintype "passive"))
      (node (ref "S107B") (pin "SW2") (pinfunction "PIN-2_SW2") (pintype "passive"))
    )
    (net (code "106") (name "Net-(S108A-PIN-1)") (class "Default")
      (node (ref "JB108") (pin "2") (pinfunction "2_2") (pintype "passive"))
      (node (ref "S108") (pin "SW1") (pinfunction "PIN-1_SW1") (pintype "passive"))
    )
    (net (code "107") (name "Net-(S108A-PIN-2)") (class "Default")
      (node (ref "JA108") (pin "1") (pinfunction "1_1") (pintype "passive"))
      (node (ref "S108") (pin "SW2") (pinfunction "PIN-2_SW2") (pintype "passive"))
    )
    (net (code "108") (name "Net-(S109A-PIN-1)") (class "Default")
      (node (ref "JB109") (pin "2") (pinfunction "2_2") (pintype "passive"))
      (node (ref "S109") (pin "SW1") (pinfunction "PIN-1_SW1") (pintype "passive"))
    )
    (net (code "109") (name "Net-(S109A-PIN-2)") (class "Default")
      (node (ref "JA109") (pin "1") (pinfunction "1_1") (pintype "passive"))
      (node (ref "S109") (pin "SW2") (pinfunction "PIN-2_SW2") (pintype "passive"))
    )
    (net (code "110") (name "Net-(S110A-PIN-1)") (class "Default")
      (node (ref "JB110") (pin "2") (pinfunction "2_2") (pintype "passive"))
      (node (ref "S110") (pin "SW1") (pinfunction "PIN-1_SW1") (pintype "passive"))
    )
    (net (code "111") (name "Net-(S110A-PIN-2)") (class "Default")
      (node (ref "JA110") (pin "1") (pinfunction "1_1") (pintype "passive"))
      (node (ref "S110") (pin "SW2") (pinfunction "PIN-2_SW2") (pintype "passive"))
    )
  )
)
